# OpenHaldexC6-V1_1_2026-01-01.net
KiCad netlist of a schematic drawn in EasyEDA Pro
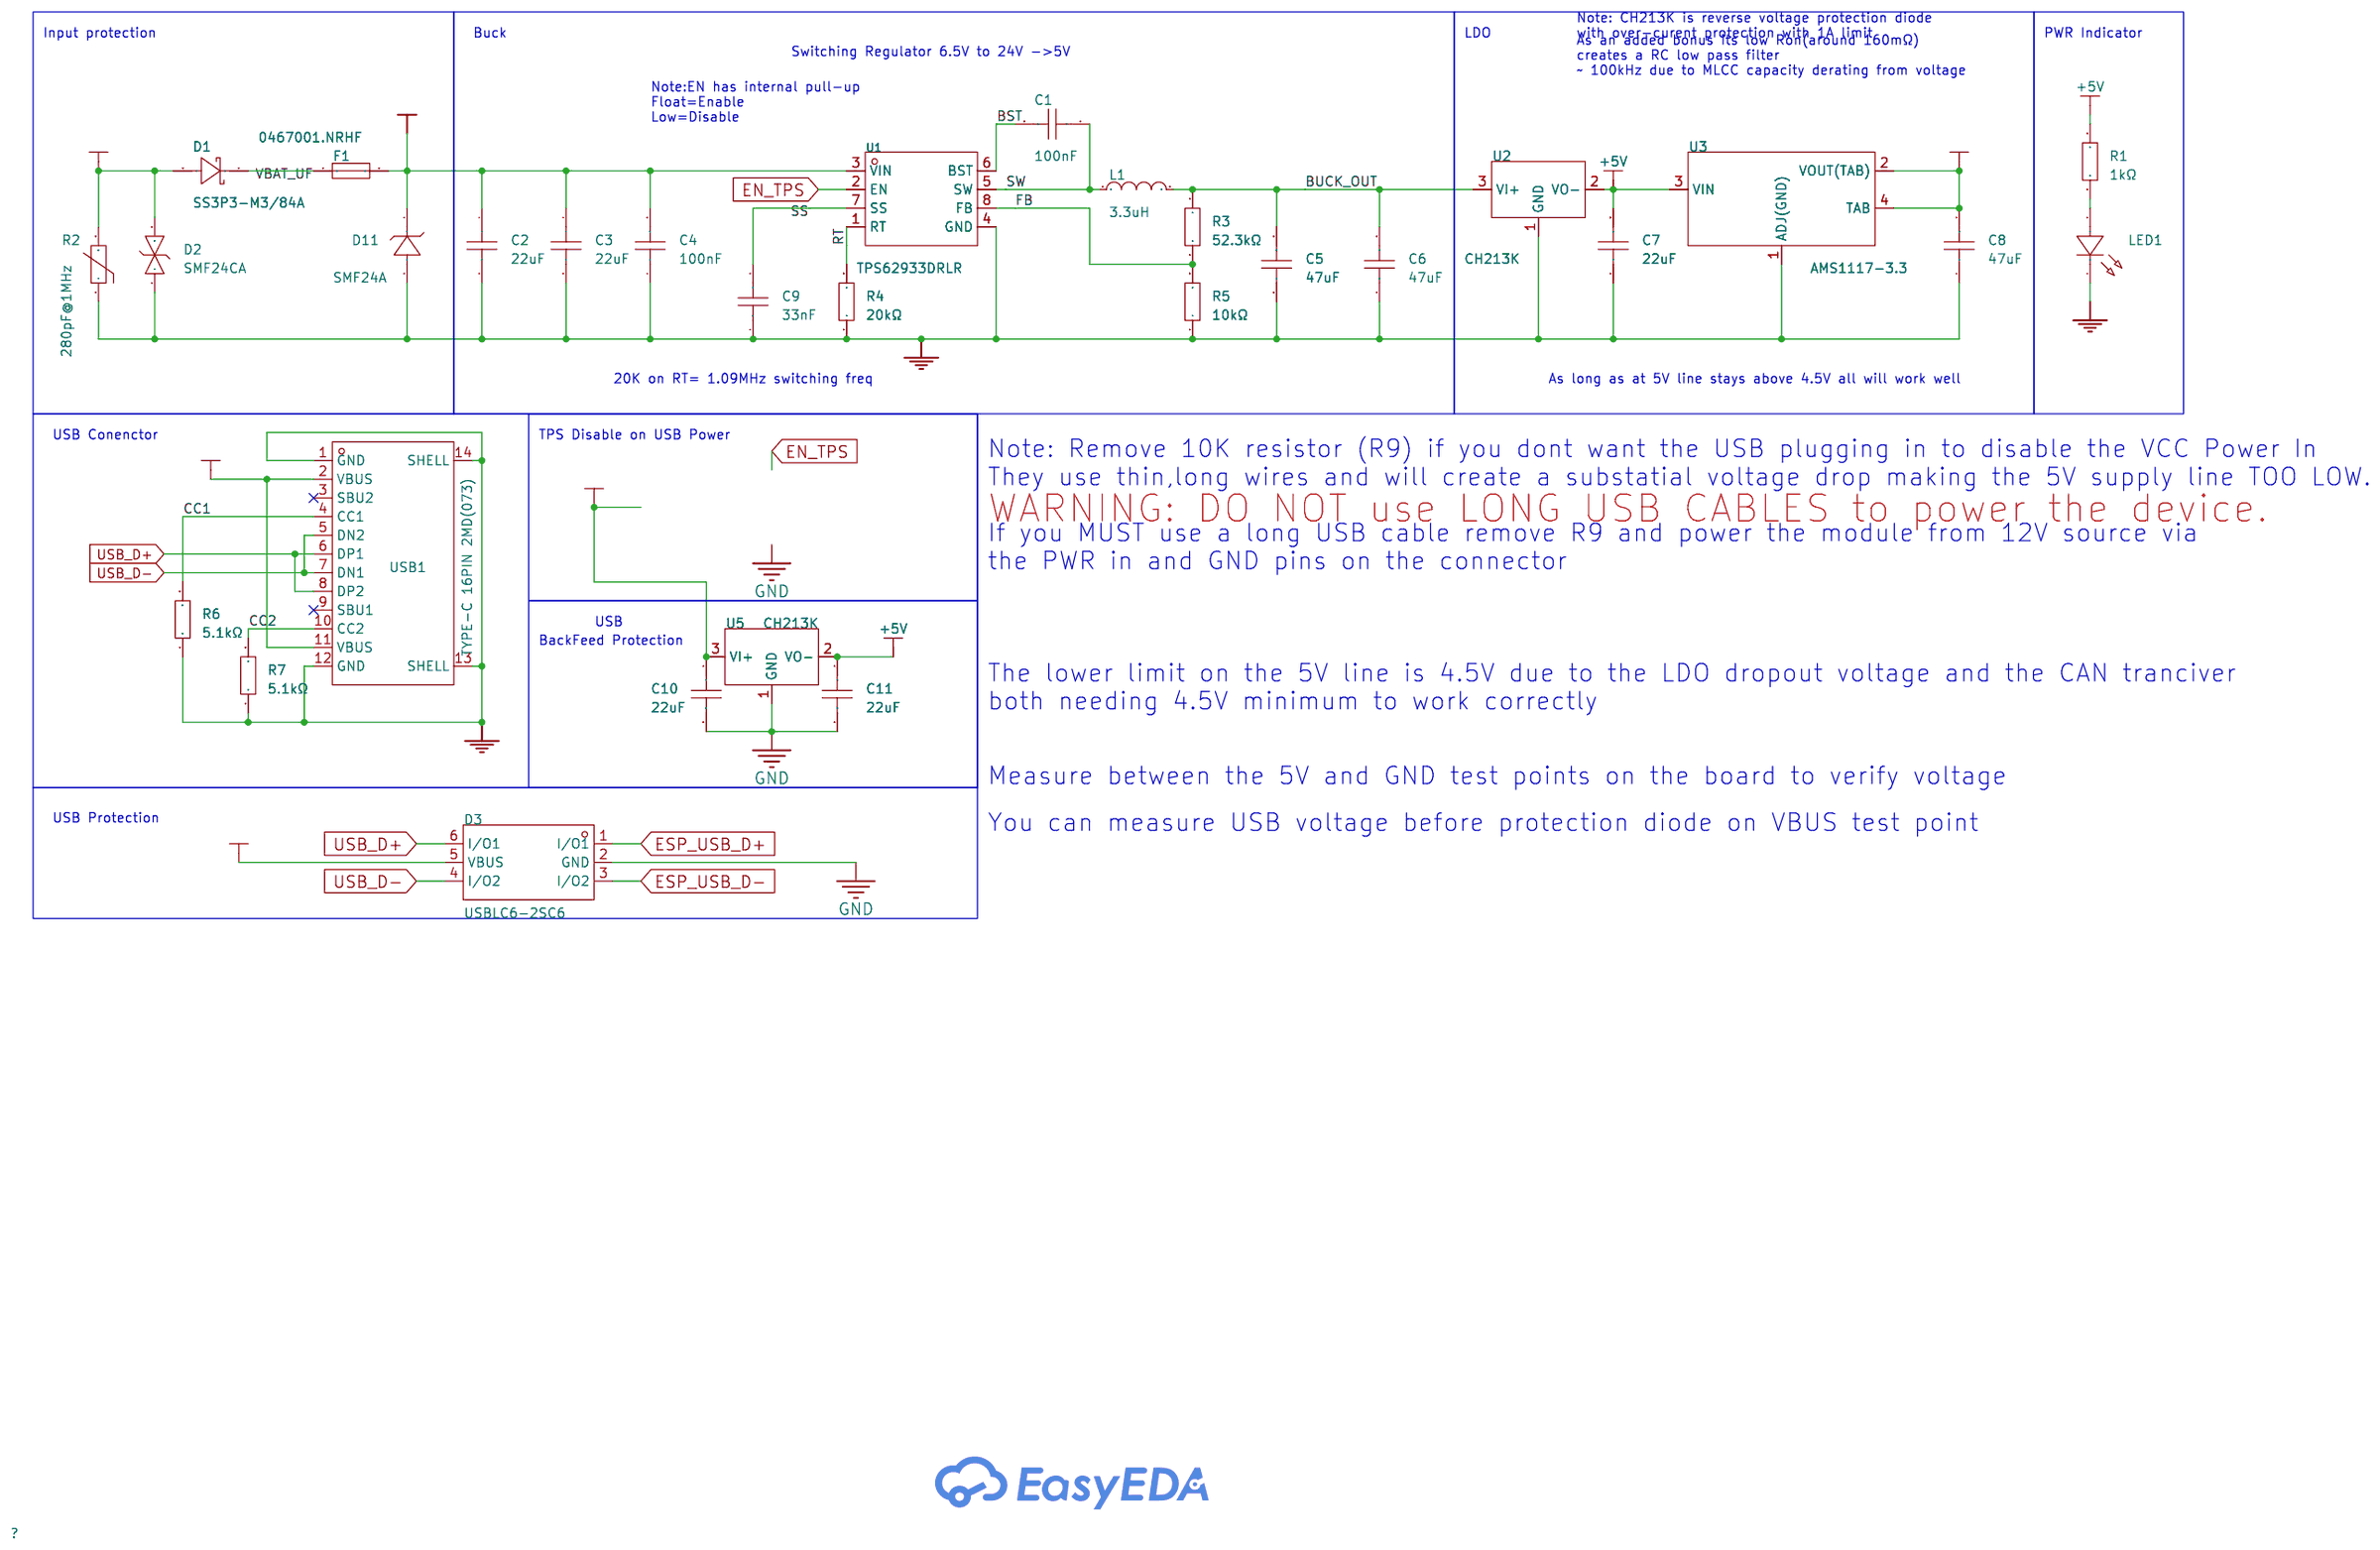
[diagram p0: Power +USB]
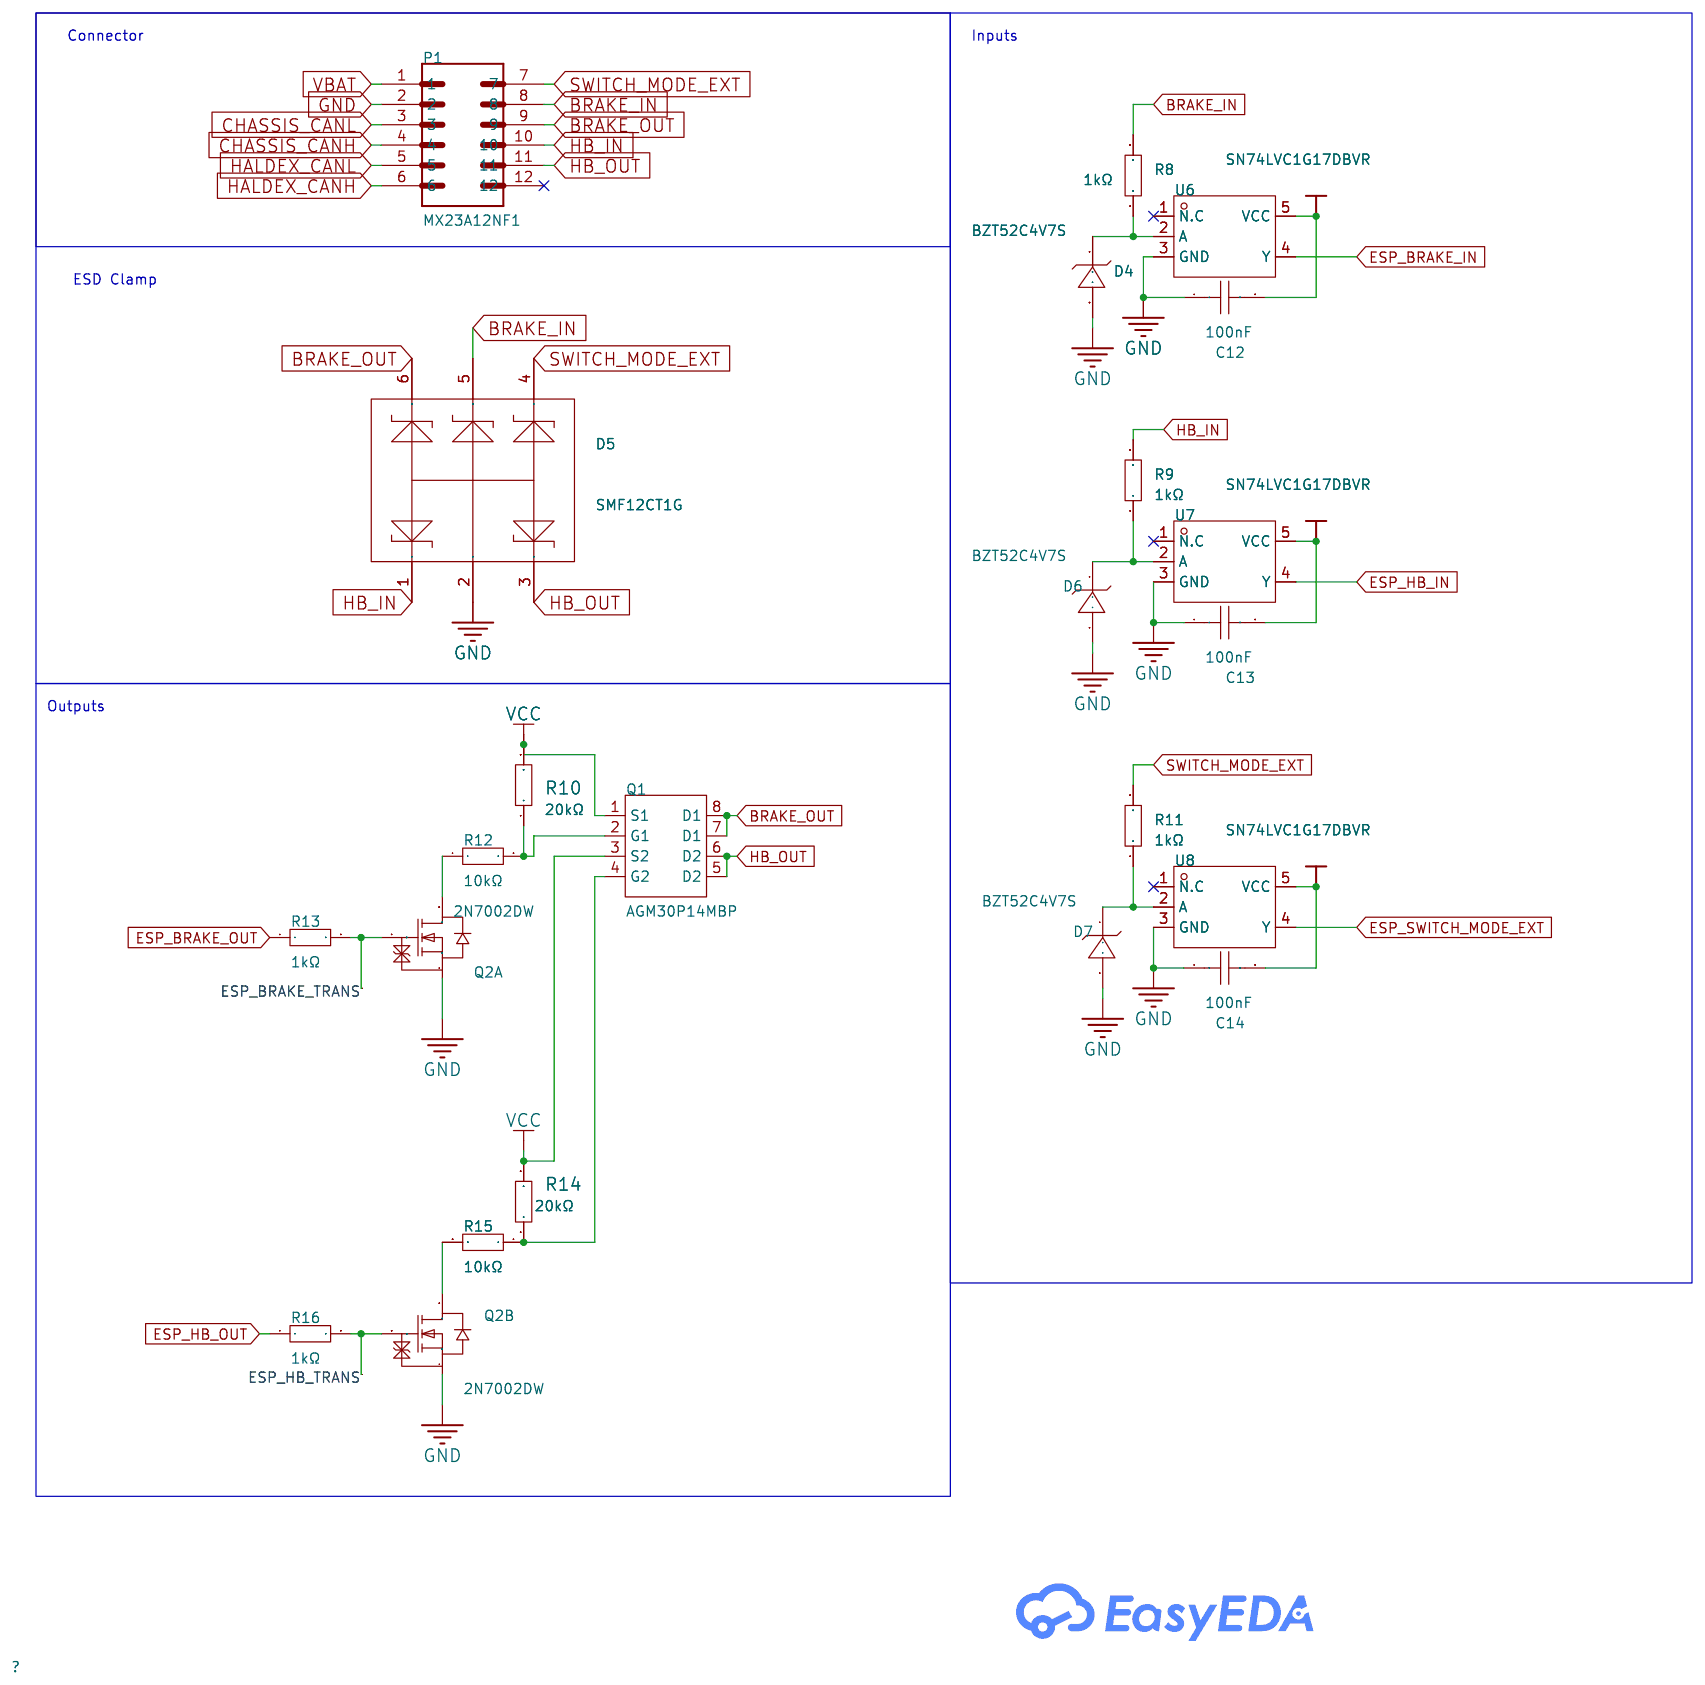
[diagram p1: Conn, Input + Output]
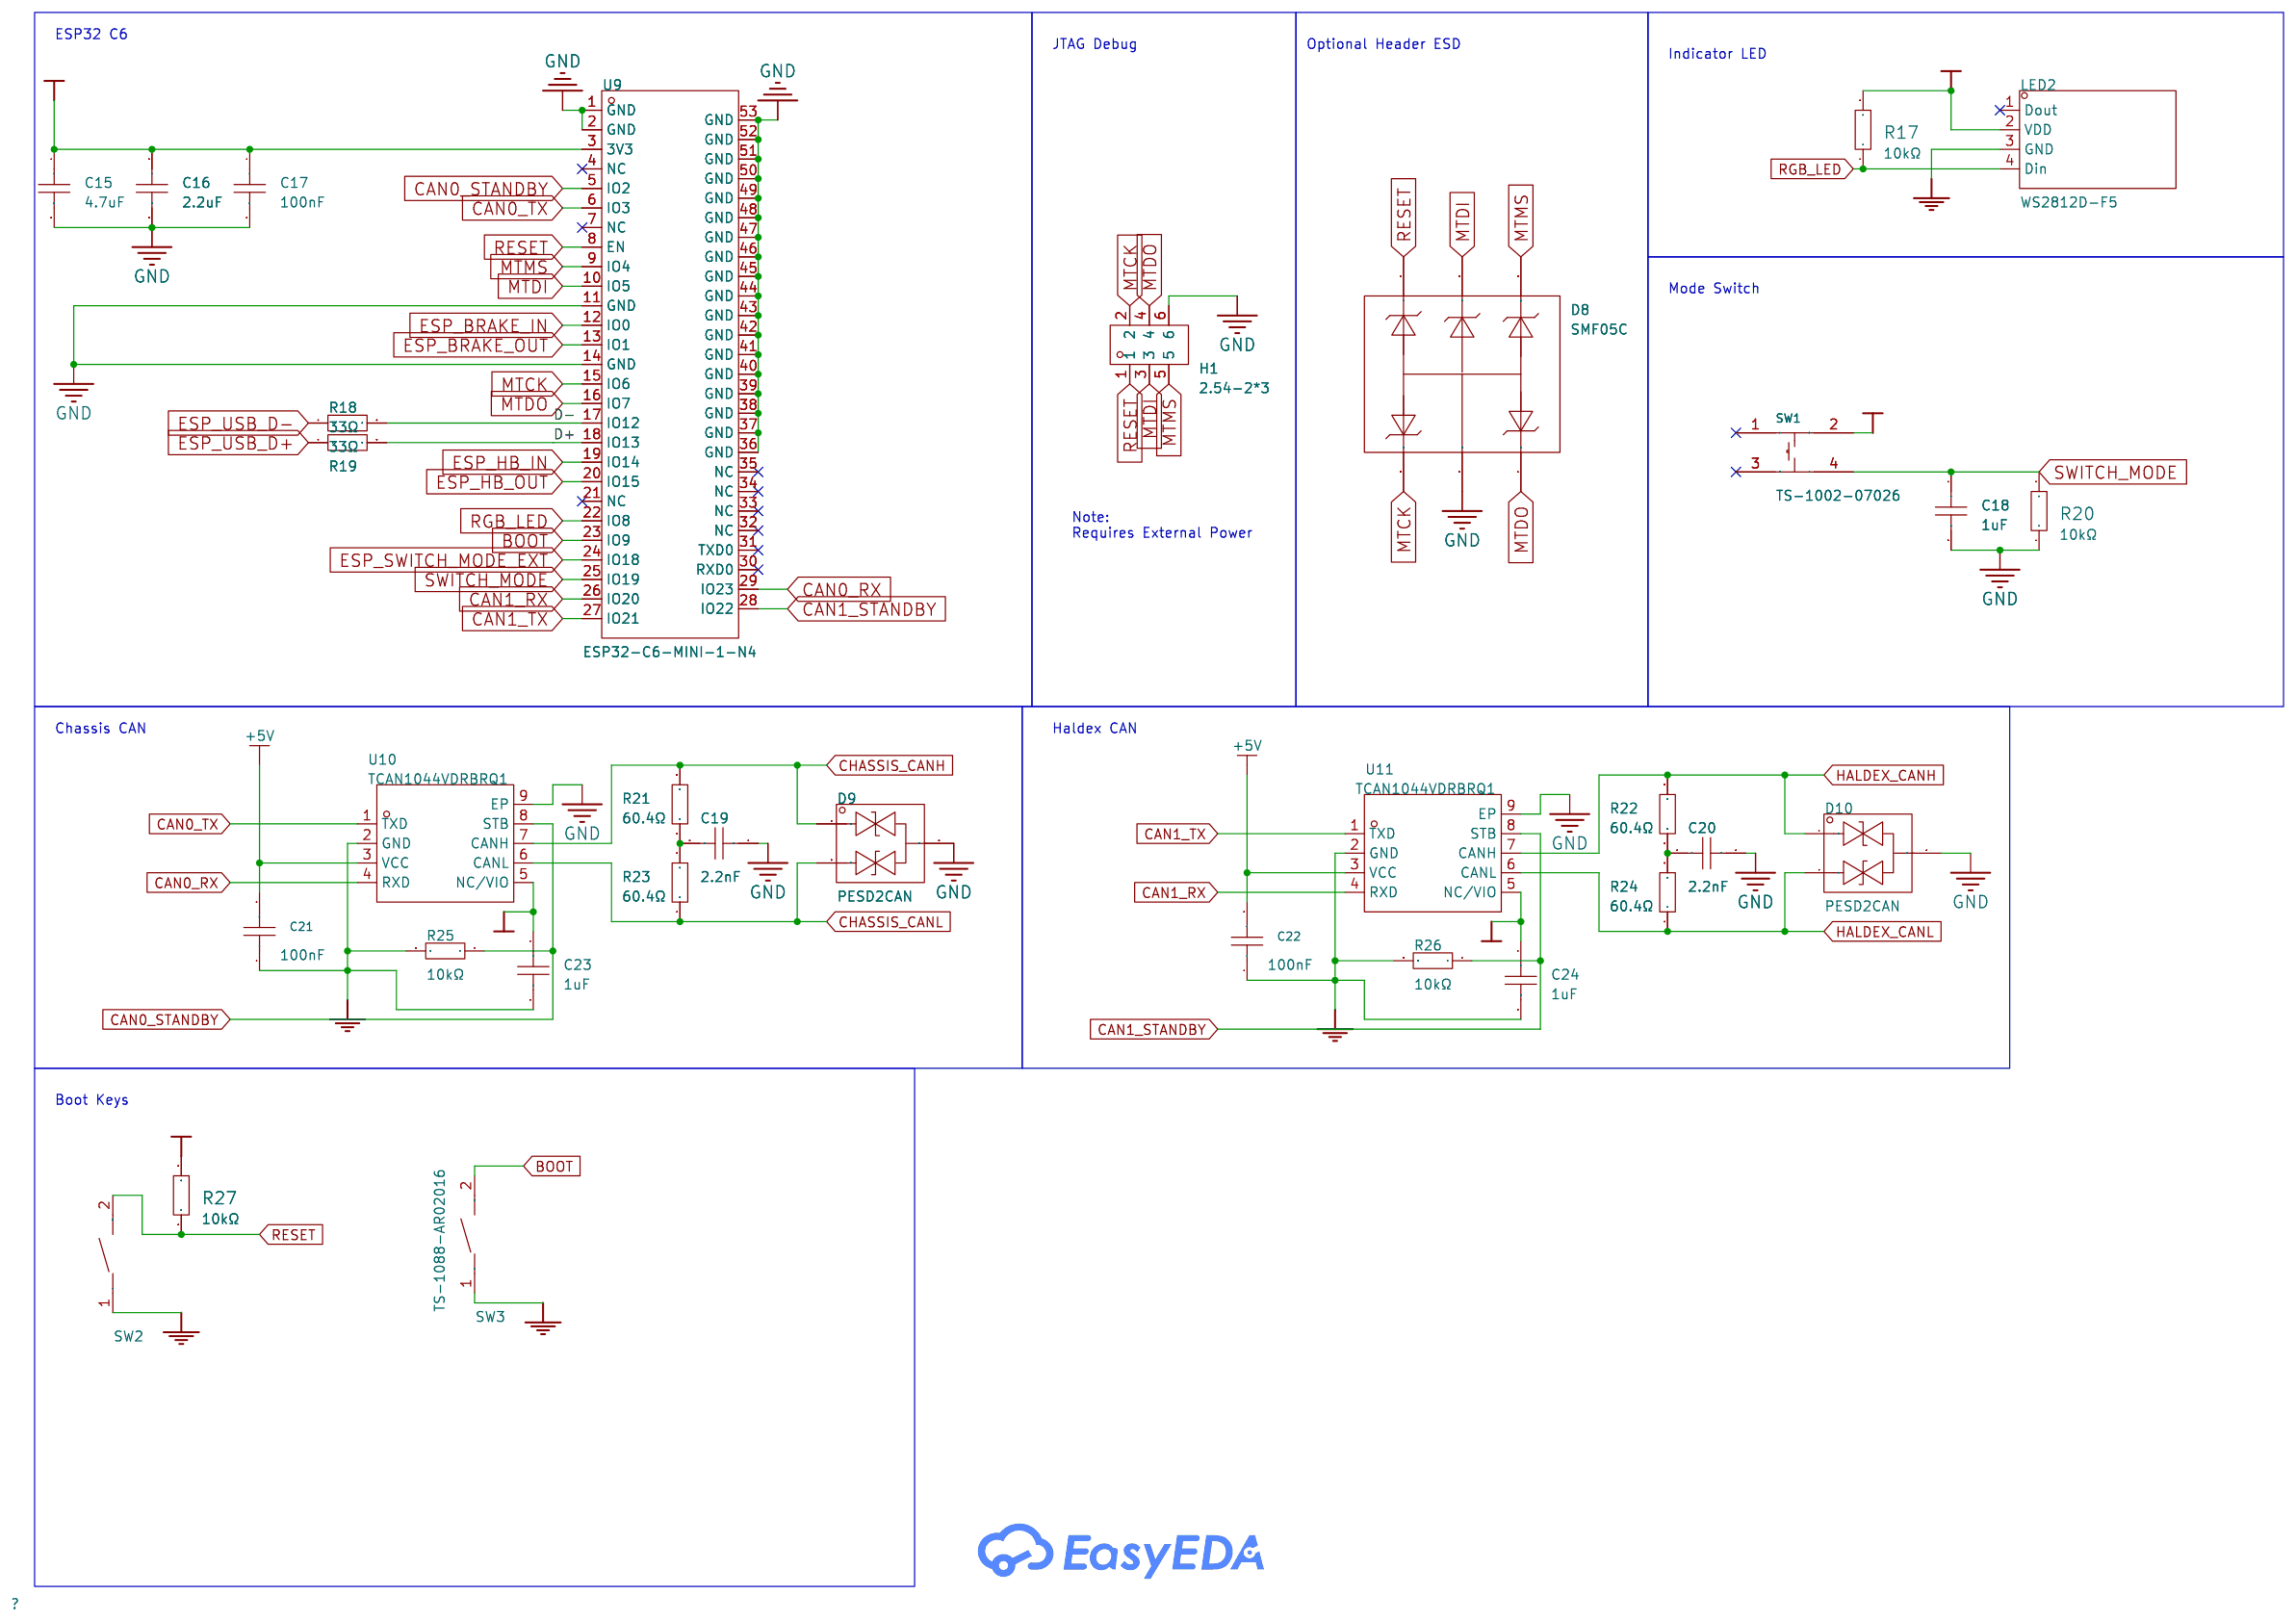
[diagram p2: MCU + CANBUS]

(export (version "E")
  (design (tool "Eeschema 10.0.6"))
  (components
    (comp (ref "C1")
      (value "100nF")
      (footprint "easyedapro:C0603")
      (description "Capacitance:100nF Tolerance:±10% Tolerance:±10% Voltage Rating:50V Temperature Coefficient:X7R")
      (fields
        (field (name "Manufacturer Part") "CL10B104KB8NNNC")
        (field (name "Manufacturer") "SAMSUNG(三星)")
      )
      (libsource (lib "easyedapro") (part "CC0603KRX7R9BB104"))
    )
    (comp (ref "C2")
      (value "22uF")
      (footprint "easyedapro:C0805")
      (fields
        (field (name "Manufacturer Part") "HGC0805R5226M350NSLJ")
        (field (name "Manufacturer") "Chinocera(华瓷)")
      )
      (libsource (lib "easyedapro") (part "HGC0805R5226M350NSLJ"))
    )
    (comp (ref "C3")
      (value "22uF")
      (footprint "easyedapro:C0805")
      (fields
        (field (name "Manufacturer Part") "HGC0805R5226M350NSLJ")
        (field (name "Manufacturer") "Chinocera(华瓷)")
      )
      (libsource (lib "easyedapro") (part "HGC0805R5226M350NSLJ"))
    )
    (comp (ref "C4")
      (value "100nF")
      (description "Capacitance:100nF Tolerance:±10% Tolerance:±10% Voltage Rating:50V Temperature Coefficient:X7R")
      (fields
        (field (name "Manufacturer Part") "CL10B104KB8NNNC")
        (field (name "Manufacturer") "SAMSUNG(三星)")
      )
      (libsource (lib "easyedapro") (part "CSA0603X7R104K500JT"))
    )
    (comp (ref "C5")
      (value "47uF")
      (footprint "easyedapro:C0805")
      (description "Capacitance:47uF Tolerance:±20% Tolerance:±20% Voltage Rating:10V Temperature Coefficient:X5R")
      (fields
        (field (name "Manufacturer Part") "CL21A476MPYNNWE")
        (field (name "Manufacturer") "SAMSUNG(三星)")
      )
      (libsource (lib "easyedapro") (part "CL21A476MPYNNWE"))
    )
    (comp (ref "C6")
      (value "47uF")
      (footprint "easyedapro:C0805")
      (description "Capacitance:47uF Tolerance:±20% Tolerance:±20% Voltage Rating:10V Temperature Coefficient:X5R")
      (fields
        (field (name "Manufacturer Part") "CL21A476MPYNNWE")
        (field (name "Manufacturer") "SAMSUNG(三星)")
      )
      (libsource (lib "easyedapro") (part "CL21A476MPYNNWE"))
    )
    (comp (ref "C7")
      (value "22uF")
      (footprint "easyedapro:C0805")
      (fields
        (field (name "Manufacturer Part") "HGC0805R5226M350NSLJ")
        (field (name "Manufacturer") "Chinocera(华瓷)")
      )
      (libsource (lib "easyedapro") (part "HGC0805R5226M350NSLJ"))
    )
    (comp (ref "C8")
      (value "47uF")
      (footprint "easyedapro:C0805")
      (description "Capacitance:47uF Tolerance:±20% Tolerance:±20% Voltage Rating:10V Temperature Coefficient:X5R")
      (fields
        (field (name "Manufacturer Part") "CL21A476MPYNNWE")
        (field (name "Manufacturer") "SAMSUNG(三星)")
      )
      (libsource (lib "easyedapro") (part "CL21A476MPYNNWE"))
    )
    (comp (ref "C9")
      (value "33nF")
      (description "Capacitance:33nF Tolerance:±10% Tolerance:±10% Voltage Rating:50V Temperature Coefficient:X7R")
      (fields
        (field (name "Manufacturer Part") "CL10B333KB8NNNC")
        (field (name "Manufacturer") "SAMSUNG(三星)")
      )
      (libsource (lib "easyedapro") (part "CSA0603X7R104K500JT"))
    )
    (comp (ref "C10")
      (value "22uF")
      (footprint "easyedapro:C0805")
      (fields
        (field (name "Manufacturer Part") "HGC0805R5226M350NSLJ")
        (field (name "Manufacturer") "Chinocera(华瓷)")
      )
      (libsource (lib "easyedapro") (part "HGC0805R5226M350NSLJ"))
    )
    (comp (ref "C11")
      (value "22uF")
      (footprint "easyedapro:C0805")
      (fields
        (field (name "Manufacturer Part") "HGC0805R5226M350NSLJ")
        (field (name "Manufacturer") "Chinocera(华瓷)")
      )
      (libsource (lib "easyedapro") (part "HGC0805R5226M350NSLJ"))
    )
    (comp (ref "D1")
      (value "SS3P3-M3/84A")
      (footprint "easyedapro:DO-220AA_L3.4-W2.0-LS3.9-RD")
      (fields (field (name "Manufacturer") "VISHAY(威世)"))
      (libsource (lib "easyedapro") (part "SS3P3-M3/84A"))
    )
    (comp (ref "D2")
      (value "SMF24CA")
      (footprint "easyedapro:SOD-123FL_L2.8-W1.8-LS3.7-BI")
      (fields (field (name "Manufacturer") "晶导微电子"))
      (libsource (lib "easyedapro") (part "SMF24CA_C353294"))
    )
    (comp (ref "D3")
      (value "USBLC6-2SC6")
      (footprint "easyedapro:SOT-23-6_L2.9-W1.6-P0.95-LS2.8-BL")
      (description "Maximum Clamping Voltage:15V Breakdown Voltage:6V Number of Lines:双路 Type:ESD")
      (fields (field (name "Manufacturer") "UMW(友台半导体)"))
      (libsource (lib "easyedapro") (part "USBLC6-2SC6_C2687116"))
    )
    (comp (ref "D11")
      (value "SMF24A")
      (footprint "easyedapro:SOD-123FL_L2.7-W1.8-LS3.8-RD")
      (fields (field (name "Manufacturer") "R+O(宏嘉诚)"))
      (libsource (lib "easyedapro") (part "SMF24A_C19077514"))
    )
    (comp (ref "F1")
      (value "0467001.NRHF")
      (footprint "easyedapro:F0603")
      (fields (field (name "Manufacturer") "Littelfuse(美国力特)"))
      (libsource (lib "easyedapro") (part "0467001.NRHF"))
    )
    (comp (ref "L1")
      (value "3.3uH")
      (footprint "easyedapro:IND-SMD_L5.4-W5.2_RS0530")
      (fields (field (name "Manufacturer Part") "RS0530-3R3MS") (field (name "Manufacturer") "Ruishen(瑞申电子)"))
      (libsource (lib "easyedapro") (part "RS0530-3R3MS"))
    )
    (comp (ref "LED1")
      (value "XL-1608UGC-04")
      (footprint "easyedapro:LED0603-RD_GREEN")
      (fields (field (name "Manufacturer") "XINGLIGHT(成兴光)"))
      (libsource (lib "easyedapro") (part "XL-1608UGC-04"))
    )
    (comp (ref "R1")
      (value "1kΩ")
      (footprint "easyedapro:R0603")
      (fields
        (field (name "Manufacturer Part") "0603WAF1001T5E")
        (field (name "Manufacturer") "UNI-ROYAL(厚声)")
      )
      (libsource (lib "easyedapro") (part "0603WAF2201T5E"))
    )
    (comp (ref "R2")
      (value "280pF@1MHz")
      (footprint "easyedapro:R0805")
      (fields (field (name "Manufacturer Part") "FPV201209E260PKT") (field (name "Manufacturer") "FH(风华)"))
      (libsource (lib "easyedapro") (part "FPV201209E260PKT"))
    )
    (comp (ref "R3")
      (value "52.3kΩ")
      (footprint "easyedapro:R0603")
      (fields
        (field (name "Manufacturer Part") "0603WAF5232T5E")
        (field (name "Manufacturer") "UNI-ROYAL(厚声)")
      )
      (libsource (lib "easyedapro") (part "Res"))
    )
    (comp (ref "R4")
      (value "20kΩ")
      (footprint "easyedapro:R0603")
      (fields
        (field (name "Manufacturer Part") "0603WAF2002T5E")
        (field (name "Manufacturer") "UNI-ROYAL(厚声)")
      )
      (libsource (lib "easyedapro") (part "Res"))
    )
    (comp (ref "R5")
      (value "10kΩ")
      (footprint "easyedapro:R0603")
      (fields
        (field (name "Manufacturer Part") "0603WAF1002T5E")
        (field (name "Manufacturer") "UNI-ROYAL(厚声)")
      )
      (libsource (lib "easyedapro") (part "Res"))
    )
    (comp (ref "R6")
      (value "5.1kΩ")
      (footprint "easyedapro:R0603")
      (fields
        (field (name "Manufacturer Part") "0603WAF5101T5E")
        (field (name "Manufacturer") "UNI-ROYAL(厚声)")
      )
      (libsource (lib "easyedapro") (part "Res"))
    )
    (comp (ref "R7")
      (value "5.1kΩ")
      (footprint "easyedapro:R0603")
      (fields
        (field (name "Manufacturer Part") "0603WAF5101T5E")
        (field (name "Manufacturer") "UNI-ROYAL(厚声)")
      )
      (libsource (lib "easyedapro") (part "Res"))
    )
    (comp (ref "U1")
      (value "TPS62933DRLR")
      (footprint "easyedapro:SOT-583-8_L2.1-W1.2-P0.50-LS1.6-BR")
      (fields (field (name "Manufacturer") "TI(德州仪器)"))
      (libsource (lib "easyedapro") (part "TPS62933DRLR"))
    )
    (comp (ref "U2")
      (value "CH213K")
      (footprint "easyedapro:SOT-23-3_L2.9-W1.6-P1.90-LS2.8-BR")
      (fields (field (name "Manufacturer") "WCH(南京沁恒)"))
      (libsource (lib "easyedapro") (part "CH213K"))
    )
    (comp (ref "U3")
      (value "AMS1117-3.3")
      (footprint "easyedapro:SOT-223-4_L6.5-W3.5-P2.30-LS7.0-BR")
      (fields (field (name "Manufacturer") "UMW(友台半导体)"))
      (libsource (lib "easyedapro") (part "AMS1117-3.3_C347222"))
    )
    (comp (ref "U5")
      (value "CH213K")
      (footprint "easyedapro:SOT-23-3_L2.9-W1.6-P1.90-LS2.8-BR")
      (fields (field (name "Manufacturer") "WCH(南京沁恒)"))
      (libsource (lib "easyedapro") (part "CH213K"))
    )
    (comp (ref "USB1")
      (value "TYPE-C 16PIN 2MD(073)")
      (footprint "easyedapro:USB-C-SMD_TYPE-C-6PIN-2MD-073")
      (fields (field (name "Manufacturer") "SHOU HAN(首韩)"))
      (libsource (lib "easyedapro") (part "TYPE-C 16PIN 2MD(073)"))
    )
    (comp (ref "C12")
      (value "100nF")
      (footprint "easyedapro:C0603")
      (description "Capacitance:100nF Tolerance:±10% Tolerance:±10% Voltage Rating:50V Temperature Coefficient:X7R")
      (fields
        (field (name "Manufacturer Part") "CL10B104KB8NNNC")
        (field (name "Manufacturer") "SAMSUNG(三星)")
      )
      (libsource (lib "easyedapro") (part "CC0603KRX7R9BB104"))
    )
    (comp (ref "C13")
      (value "100nF")
      (footprint "easyedapro:C0603")
      (description "Capacitance:100nF Tolerance:±10% Tolerance:±10% Voltage Rating:50V Temperature Coefficient:X7R")
      (fields
        (field (name "Manufacturer Part") "CL10B104KB8NNNC")
        (field (name "Manufacturer") "SAMSUNG(三星)")
      )
      (libsource (lib "easyedapro") (part "CC0603KRX7R9BB104"))
    )
    (comp (ref "C14")
      (value "100nF")
      (footprint "easyedapro:C0603")
      (description "Capacitance:100nF Tolerance:±10% Tolerance:±10% Voltage Rating:50V Temperature Coefficient:X7R")
      (fields
        (field (name "Manufacturer Part") "CL10B104KB8NNNC")
        (field (name "Manufacturer") "SAMSUNG(三星)")
      )
      (libsource (lib "easyedapro") (part "CC0603KRX7R9BB104"))
    )
    (comp (ref "D4")
      (value "BZT52C4V7S")
      (footprint "easyedapro:SOD-323_L1.8-W1.3-LS2.5-RD")
      (fields (field (name "Manufacturer") "晶导微电子"))
      (libsource (lib "easyedapro") (part "BZT52C4V7S_C353517"))
    )
    (comp (ref "D5")
      (value "SMF12CT1G")
      (footprint "easyedapro:SOT-363_L2.0-W1.3-P0.65-LS2.1-BR")
      (fields (field (name "Manufacturer") "TECH PUBLIC(台舟)"))
      (libsource (lib "easyedapro") (part "SMF12CT1G_C2999118"))
    )
    (comp (ref "D6")
      (value "BZT52C4V7S")
      (footprint "easyedapro:SOD-323_L1.8-W1.3-LS2.5-RD")
      (fields (field (name "Manufacturer") "晶导微电子"))
      (libsource (lib "easyedapro") (part "BZT52C4V7S_C353517"))
    )
    (comp (ref "D7")
      (value "BZT52C4V7S")
      (footprint "easyedapro:SOD-323_L1.8-W1.3-LS2.5-RD")
      (fields (field (name "Manufacturer") "晶导微电子"))
      (libsource (lib "easyedapro") (part "BZT52C4V7S_C353517"))
    )
    (comp (ref "P1")
      (value "MX23A12NF1")
      (fields (field (name "Manufacturer") "JAE(日本航空电子)"))
      (libsource (lib "easyedapro") (part "MX23A12NF1_MX23A12NF1_"))
    )
    (comp (ref "Q1")
      (value "AGM30P14MBP")
      (footprint "easyedapro:DFN-8_L3.2-W3.1-P0.65-LS3.4-BL-1")
      (fields (field (name "Manufacturer") "AGMSEMI(芯控源)"))
      (libsource (lib "easyedapro") (part "AGM30P14MBP"))
    )
    (comp (ref "Q2")
      (value "2N7002DW")
      (footprint "easyedapro:SOT-363-6_L2.0-W1.3-P0.65-LS2.1-BL")
      (fields (field (name "Manufacturer") "Hottech(合科泰)"))
      (libsource (lib "easyedapro") (part "2N7002DW_C5190214"))
    )
    (comp (ref "R8")
      (value "1kΩ")
      (footprint "easyedapro:R0603")
      (fields
        (field (name "Manufacturer Part") "0603WAF1001T5E")
        (field (name "Manufacturer") "UNI-ROYAL(厚声)")
      )
      (libsource (lib "easyedapro") (part "0603WAF1001T5E"))
    )
    (comp (ref "R9")
      (value "1kΩ")
      (footprint "easyedapro:R0603")
      (fields
        (field (name "Manufacturer Part") "0603WAF1001T5E")
        (field (name "Manufacturer") "UNI-ROYAL(厚声)")
      )
      (libsource (lib "easyedapro") (part "0603WAF1001T5E"))
    )
    (comp (ref "R10")
      (value "20kΩ")
      (footprint "easyedapro:R0603")
      (fields
        (field (name "Manufacturer Part") "0603WAF2002T5E")
        (field (name "Manufacturer") "UNI-ROYAL(厚声)")
      )
      (libsource (lib "easyedapro") (part "0603WAF1002T5E"))
    )
    (comp (ref "R11")
      (value "1kΩ")
      (footprint "easyedapro:R0603")
      (fields
        (field (name "Manufacturer Part") "0603WAF1001T5E")
        (field (name "Manufacturer") "UNI-ROYAL(厚声)")
      )
      (libsource (lib "easyedapro") (part "0603WAF1001T5E"))
    )
    (comp (ref "R12")
      (value "10kΩ")
      (footprint "easyedapro:R0603")
      (fields
        (field (name "Manufacturer Part") "0603WAF1002T5E")
        (field (name "Manufacturer") "UNI-ROYAL(厚声)")
      )
      (libsource (lib "easyedapro") (part "Res"))
    )
    (comp (ref "R13")
      (value "1kΩ")
      (footprint "easyedapro:R0603")
      (fields
        (field (name "Manufacturer Part") "0603WAF1001T5E")
        (field (name "Manufacturer") "UNI-ROYAL(厚声)")
      )
      (libsource (lib "easyedapro") (part "0603WAF3300T5E"))
    )
    (comp (ref "R14")
      (value "20kΩ")
      (footprint "easyedapro:R0603")
      (fields
        (field (name "Manufacturer Part") "0603WAF2002T5E")
        (field (name "Manufacturer") "UNI-ROYAL(厚声)")
      )
      (libsource (lib "easyedapro") (part "0603WAF1002T5E"))
    )
    (comp (ref "R15")
      (value "10kΩ")
      (footprint "easyedapro:R0603")
      (fields
        (field (name "Manufacturer Part") "0603WAF1002T5E")
        (field (name "Manufacturer") "UNI-ROYAL(厚声)")
      )
      (libsource (lib "easyedapro") (part "Res"))
    )
    (comp (ref "R16")
      (value "1kΩ")
      (footprint "easyedapro:R0603")
      (fields
        (field (name "Manufacturer Part") "0603WAF1001T5E")
        (field (name "Manufacturer") "UNI-ROYAL(厚声)")
      )
      (libsource (lib "easyedapro") (part "0603WAF3300T5E"))
    )
    (comp (ref "U6")
      (value "SN74LVC1G17DBVR")
      (footprint "easyedapro:SOT-23-5_L3.0-W1.5-P0.95-LS2.8-BL")
      (fields (field (name "Manufacturer") "TECH PUBLIC(台舟)"))
      (libsource (lib "easyedapro") (part "SN74LVC1G17DBVR_C19829662"))
    )
    (comp (ref "U7")
      (value "SN74LVC1G17DBVR")
      (footprint "easyedapro:SOT-23-5_L3.0-W1.5-P0.95-LS2.8-BL")
      (fields (field (name "Manufacturer") "TECH PUBLIC(台舟)"))
      (libsource (lib "easyedapro") (part "SN74LVC1G17DBVR_C19829662"))
    )
    (comp (ref "U8")
      (value "SN74LVC1G17DBVR")
      (footprint "easyedapro:SOT-23-5_L3.0-W1.5-P0.95-LS2.8-BL")
      (fields (field (name "Manufacturer") "TECH PUBLIC(台舟)"))
      (libsource (lib "easyedapro") (part "SN74LVC1G17DBVR_C19829662"))
    )
    (comp (ref "C15")
      (value "4.7uF")
      (footprint "easyedapro:C0603")
      (description "Capacitance:4.7uF Tolerance:±10% Tolerance:±10% Voltage Rating:10V Temperature Coefficient:X5R")
      (fields
        (field (name "Manufacturer Part") "CL10A475KP8NNNC")
        (field (name "Manufacturer") "SAMSUNG(三星)")
      )
      (libsource (lib "easyedapro") (part "CAP"))
    )
    (comp (ref "C16")
      (value "2.2uF")
      (footprint "easyedapro:C0603")
      (description "Capacitance:2.2uF Tolerance:±10% Tolerance:±10% Voltage Rating:16V Temperature Coefficient:X5R")
      (fields
        (field (name "Manufacturer Part") "CL10A225KO8NNNC")
        (field (name "Manufacturer") "SAMSUNG(三星)")
      )
      (libsource (lib "easyedapro") (part "CAP"))
    )
    (comp (ref "C17")
      (value "100nF")
      (footprint "easyedapro:C0603")
      (description "Capacitance:100nF Tolerance:±10% Tolerance:±10% Voltage Rating:50V Temperature Coefficient:X7R")
      (fields
        (field (name "Manufacturer Part") "CL10B104KB8NNNC")
        (field (name "Manufacturer") "SAMSUNG(三星)")
      )
      (libsource (lib "easyedapro") (part "CAP"))
    )
    (comp (ref "C18")
      (value "1uF")
      (footprint "easyedapro:C0603")
      (description "Capacitance:1uF Tolerance:±10% Tolerance:±10% Voltage Rating:50V Temperature Coefficient:X7R")
      (fields
        (field (name "Manufacturer Part") "CL10B105KB8NQNC")
        (field (name "Manufacturer") "SAMSUNG(三星)")
      )
      (libsource (lib "easyedapro") (part "CL10B105KB8NQNC"))
    )
    (comp (ref "C19")
      (value "2.2nF")
      (footprint "easyedapro:C0603")
      (description "Capacitance:2.2nF Tolerance:±5% Tolerance:±5% Voltage Rating:50V Temperature Coefficient:C0G")
      (fields
        (field (name "Manufacturer Part") "CL10C222JB8NNNC")
        (field (name "Manufacturer") "SAMSUNG(三星)")
      )
      (libsource (lib "easyedapro") (part "CAP"))
    )
    (comp (ref "C20")
      (value "2.2nF")
      (footprint "easyedapro:C0603")
      (description "Capacitance:2.2nF Tolerance:±5% Tolerance:±5% Voltage Rating:50V Temperature Coefficient:C0G")
      (fields
        (field (name "Manufacturer Part") "CL10C222JB8NNNC")
        (field (name "Manufacturer") "SAMSUNG(三星)")
      )
      (libsource (lib "easyedapro") (part "CAP"))
    )
    (comp (ref "C21")
      (value "100nF")
      (footprint "easyedapro:C0603")
      (description "Capacitance:100nF Tolerance:±10% Tolerance:±10% Voltage Rating:50V Temperature Coefficient:X7R")
      (fields
        (field (name "Manufacturer Part") "CL10B104KB8NNNC")
        (field (name "Manufacturer") "SAMSUNG(三星)")
      )
      (libsource (lib "easyedapro") (part "CL10B104KB8NNNC"))
    )
    (comp (ref "C22")
      (value "100nF")
      (footprint "easyedapro:C0603")
      (description "Capacitance:100nF Tolerance:±10% Tolerance:±10% Voltage Rating:50V Temperature Coefficient:X7R")
      (fields
        (field (name "Manufacturer Part") "CL10B104KB8NNNC")
        (field (name "Manufacturer") "SAMSUNG(三星)")
      )
      (libsource (lib "easyedapro") (part "CL10B104KB8NNNC"))
    )
    (comp (ref "C23")
      (value "1uF")
      (footprint "easyedapro:C0603")
      (description "Capacitance:1uF Tolerance:±10% Tolerance:±10% Voltage Rating:50V Temperature Coefficient:X7R")
      (fields
        (field (name "Manufacturer Part") "CL10B105KB8NQNC")
        (field (name "Manufacturer") "SAMSUNG(三星)")
      )
      (libsource (lib "easyedapro") (part "CAP"))
    )
    (comp (ref "C24")
      (value "1uF")
      (footprint "easyedapro:C0603")
      (description "Capacitance:1uF Tolerance:±10% Tolerance:±10% Voltage Rating:50V Temperature Coefficient:X7R")
      (fields
        (field (name "Manufacturer Part") "CL10B105KB8NQNC")
        (field (name "Manufacturer") "SAMSUNG(三星)")
      )
      (libsource (lib "easyedapro") (part "CAP"))
    )
    (comp (ref "D8")
      (value "SMF05C")
      (footprint "easyedapro:SC-70-6_L2.0-W1.3-P0.65-LS2.1-BR")
      (fields (field (name "Manufacturer") "TECH PUBLIC(台舟)"))
      (libsource (lib "easyedapro") (part "SMF05C_C558425"))
    )
    (comp (ref "D9")
      (value "PESD2CAN")
      (footprint "easyedapro:SOT-23-3_L2.9-W1.3-P1.90-LS2.4-BR")
      (fields (field (name "Manufacturer") "DOWO(东沃)"))
      (libsource (lib "easyedapro") (part "PESD2CAN"))
    )
    (comp (ref "D10")
      (value "PESD2CAN")
      (footprint "easyedapro:SOT-23-3_L2.9-W1.3-P1.90-LS2.4-BR")
      (fields (field (name "Manufacturer") "DOWO(东沃)"))
      (libsource (lib "easyedapro") (part "PESD2CAN"))
    )
    (comp (ref "H1")
      (value "2.54-2*3")
      (footprint "easyedapro:HDR-TH_6P-P2.54-V-R2-C3-S2.54_A2541WV-2X3P")
      (fields (field (name "Manufacturer") "ZHOURI(洲日)"))
      (libsource (lib "easyedapro") (part "2.54-2*3"))
    )
    (comp (ref "LED2")
      (value "WS2812D-F5")
      (footprint "easyedapro:LED-TH_4P-BD5.8-P1.30")
      (fields (field (name "Manufacturer") "worldsemi"))
      (libsource (lib "easyedapro") (part "WS2812D-F5"))
    )
    (comp (ref "R17")
      (value "10kΩ")
      (footprint "easyedapro:R0603")
      (fields
        (field (name "Manufacturer Part") "0603WAF1002T5E")
        (field (name "Manufacturer") "UNI-ROYAL(厚声)")
      )
      (libsource (lib "easyedapro") (part "0603WAF1002T5E"))
    )
    (comp (ref "R18")
      (value "33Ω")
      (footprint "easyedapro:R0603")
      (fields
        (field (name "Manufacturer Part") "0603WAF330JT5E")
        (field (name "Manufacturer") "UNI-ROYAL(厚声)")
      )
      (libsource (lib "easyedapro") (part "Res"))
    )
    (comp (ref "R19")
      (value "33Ω")
      (footprint "easyedapro:R0603")
      (fields
        (field (name "Manufacturer Part") "0603WAF330JT5E")
        (field (name "Manufacturer") "UNI-ROYAL(厚声)")
      )
      (libsource (lib "easyedapro") (part "Res"))
    )
    (comp (ref "R20")
      (value "10kΩ")
      (footprint "easyedapro:R0603")
      (fields
        (field (name "Manufacturer Part") "0603WAF1002T5E")
        (field (name "Manufacturer") "UNI-ROYAL(厚声)")
      )
      (libsource (lib "easyedapro") (part "0603WAF1002T5E"))
    )
    (comp (ref "R21")
      (value "60.4Ω")
      (footprint "easyedapro:R0603")
      (fields (field (name "Manufacturer Part") "RC0603FR-0760R4L") (field (name "Manufacturer") "YAGEO(国巨)"))
      (libsource (lib "easyedapro") (part "RC0603FR-0760R4L"))
    )
    (comp (ref "R22")
      (value "60.4Ω")
      (footprint "easyedapro:R0603")
      (fields (field (name "Manufacturer Part") "RC0603FR-0760R4L") (field (name "Manufacturer") "YAGEO(国巨)"))
      (libsource (lib "easyedapro") (part "RC0603FR-0760R4L"))
    )
    (comp (ref "R23")
      (value "60.4Ω")
      (footprint "easyedapro:R0603")
      (fields (field (name "Manufacturer Part") "RC0603FR-0760R4L") (field (name "Manufacturer") "YAGEO(国巨)"))
      (libsource (lib "easyedapro") (part "RC0603FR-0760R4L"))
    )
    (comp (ref "R24")
      (value "60.4Ω")
      (footprint "easyedapro:R0603")
      (fields (field (name "Manufacturer Part") "RC0603FR-0760R4L") (field (name "Manufacturer") "YAGEO(国巨)"))
      (libsource (lib "easyedapro") (part "RC0603FR-0760R4L"))
    )
    (comp (ref "R25")
      (value "10kΩ")
      (footprint "easyedapro:R0603")
      (fields
        (field (name "Manufacturer Part") "0603WAF1002T5E")
        (field (name "Manufacturer") "UNI-ROYAL(厚声)")
      )
      (libsource (lib "easyedapro") (part "0603WAF1002T5E"))
    )
    (comp (ref "R26")
      (value "10kΩ")
      (footprint "easyedapro:R0603")
      (fields
        (field (name "Manufacturer Part") "0603WAF1002T5E")
        (field (name "Manufacturer") "UNI-ROYAL(厚声)")
      )
      (libsource (lib "easyedapro") (part "0603WAF1002T5E"))
    )
    (comp (ref "R27")
      (value "10kΩ")
      (footprint "easyedapro:R0603")
      (fields
        (field (name "Manufacturer Part") "0603WAF1002T5E")
        (field (name "Manufacturer") "UNI-ROYAL(厚声)")
      )
      (libsource (lib "easyedapro") (part "0603WAF1002T5E"))
    )
    (comp (ref "SW1")
      (value "TS-1002-07026")
      (footprint "easyedapro:SW-TH_4P-L6.0-W6.0-P4.50-LS6.5")
      (fields (field (name "Manufacturer") "XUNPU(讯普)"))
      (libsource (lib "easyedapro") (part "TS-1002-07026"))
    )
    (comp (ref "SW2")
      (value "TS-1088-AR02016")
      (footprint "easyedapro:SW-SMD_L3.9-W3.0-P4.45")
      (fields (field (name "Manufacturer") "XUNPU(讯普)"))
      (libsource (lib "easyedapro") (part "TS-1088-AR02016"))
    )
    (comp (ref "SW3")
      (value "TS-1088-AR02016")
      (footprint "easyedapro:SW-SMD_L3.9-W3.0-P4.45")
      (fields (field (name "Manufacturer") "XUNPU(讯普)"))
      (libsource (lib "easyedapro") (part "TS-1088-AR02016"))
    )
    (comp (ref "U9")
      (value "ESP32-C6-MINI-1-N4")
      (footprint "easyedapro:WIFIM-SMD_61P-L16.6-W13.2-P0.80-ESP32-C6-MINI-1-N4")
      (fields (field (name "Manufacturer") "ESPRESSIF(乐鑫)"))
      (libsource (lib "easyedapro") (part "ESP32-C6-MINI-1-N4"))
    )
    (comp (ref "U10")
      (value "TCAN1044VDRBRQ1")
      (footprint "easyedapro:VSON-8_L3.0-W3.0-P0.65-BR-EP")
      (fields (field (name "Manufacturer") "TI(德州仪器)"))
      (libsource (lib "easyedapro") (part "TCAN1044VDRBRQ1"))
    )
    (comp (ref "U11")
      (value "TCAN1044VDRBRQ1")
      (footprint "easyedapro:VSON-8_L3.0-W3.0-P0.65-BR-EP")
      (fields (field (name "Manufacturer") "TI(德州仪器)"))
      (libsource (lib "easyedapro") (part "TCAN1044VDRBRQ1"))
    )
  )
  (nets
    (net (code "1") (name "+3.3V") (class "Default")
      (node (ref "C12") (pin "2") (pinfunction "2_2") (pintype "unspecified"))
      (node (ref "C13") (pin "2") (pinfunction "2_2") (pintype "unspecified"))
      (node (ref "C14") (pin "2") (pinfunction "2_2") (pintype "unspecified"))
      (node (ref "C15") (pin "1") (pinfunction "1_1") (pintype "input"))
      (node (ref "C16") (pin "1") (pinfunction "1_1") (pintype "input"))
      (node (ref "C17") (pin "1") (pinfunction "1_1") (pintype "input"))
      (node (ref "C23") (pin "1") (pinfunction "1_1") (pintype "input"))
      (node (ref "C24") (pin "1") (pinfunction "1_1") (pintype "input"))
      (node (ref "C8") (pin "2") (pinfunction "2_2") (pintype "unspecified"))
      (node (ref "LED2") (pin "2") (pinfunction "VDD_2") (pintype "unspecified"))
      (node (ref "R17") (pin "2") (pinfunction "2_2") (pintype "input"))
      (node (ref "R27") (pin "2") (pinfunction "2_2") (pintype "input"))
      (node (ref "SW1") (pin "2") (pinfunction "2_2") (pintype "input"))
      (node (ref "U10") (pin "5") (pinfunction "NC/VIO_5") (pintype "unspecified"))
      (node (ref "U11") (pin "5") (pinfunction "NC/VIO_5") (pintype "unspecified"))
      (node (ref "U3") (pin "2") (pinfunction "VOUT(TAB)_2") (pintype "unspecified"))
      (node (ref "U3") (pin "4") (pinfunction "TAB_4") (pintype "unspecified"))
      (node (ref "U6") (pin "5") (pinfunction "VCC_5") (pintype "unspecified"))
      (node (ref "U7") (pin "5") (pinfunction "VCC_5") (pintype "unspecified"))
      (node (ref "U8") (pin "5") (pinfunction "VCC_5") (pintype "unspecified"))
      (node (ref "U9") (pin "3") (pinfunction "3V3_3") (pintype "unspecified"))
    )
    (net (code "2") (name "+5V") (class "Default")
      (node (ref "C11") (pin "1") (pinfunction "1_1") (pintype "unspecified"))
      (node (ref "C21") (pin "2") (pinfunction "2_2") (pintype "input"))
      (node (ref "C22") (pin "2") (pinfunction "2_2") (pintype "input"))
      (node (ref "C7") (pin "2") (pinfunction "2_2") (pintype "unspecified"))
      (node (ref "R1") (pin "2") (pinfunction "2_2") (pintype "input"))
      (node (ref "U10") (pin "3") (pinfunction "VCC_3") (pintype "unspecified"))
      (node (ref "U11") (pin "3") (pinfunction "VCC_3") (pintype "unspecified"))
      (node (ref "U2") (pin "2") (pinfunction "VO-_2") (pintype "unspecified"))
      (node (ref "U3") (pin "3") (pinfunction "VIN_3") (pintype "unspecified"))
      (node (ref "U5") (pin "2") (pinfunction "VO-_2") (pintype "unspecified"))
    )
    (net (code "3") (name "BOOT") (class "Default")
      (node (ref "SW3") (pin "2") (pinfunction "2_2") (pintype "unspecified"))
      (node (ref "U9") (pin "23") (pinfunction "IO9_23") (pintype "unspecified"))
    )
    (net (code "4") (name "BRAKE_IN") (class "Default")
      (node (ref "D5") (pin "5") (pinfunction "5_5") (pintype "input"))
      (node (ref "P1") (pin "8") (pinfunction "8_8") (pintype "unspecified"))
      (node (ref "R8") (pin "2") (pinfunction "2_2") (pintype "input"))
    )
    (net (code "5") (name "BRAKE_OUT") (class "Default")
      (node (ref "D5") (pin "6") (pinfunction "6_6") (pintype "input"))
      (node (ref "P1") (pin "9") (pinfunction "9_9") (pintype "unspecified"))
      (node (ref "Q1") (pin "7") (pinfunction "D1_7") (pintype "unspecified"))
      (node (ref "Q1") (pin "8") (pinfunction "D1_8") (pintype "unspecified"))
    )
    (net (code "6") (name "BST") (class "Default")
      (node (ref "C1") (pin "2") (pinfunction "2_2") (pintype "unspecified"))
      (node (ref "U1") (pin "6") (pinfunction "BST_6") (pintype "input"))
    )
    (net (code "7") (name "BUCK_OUT") (class "Default")
      (node (ref "C5") (pin "2") (pinfunction "2_2") (pintype "unspecified"))
      (node (ref "C6") (pin "2") (pinfunction "2_2") (pintype "unspecified"))
      (node (ref "L1") (pin "2") (pinfunction "2_2") (pintype "unspecified"))
      (node (ref "R3") (pin "2") (pinfunction "2_2") (pintype "input"))
      (node (ref "U2") (pin "3") (pinfunction "VI+_3") (pintype "unspecified"))
    )
    (net (code "8") (name "CAN0_RX") (class "Default")
      (node (ref "U10") (pin "4") (pinfunction "RXD_4") (pintype "unspecified"))
      (node (ref "U9") (pin "29") (pinfunction "IO23_29") (pintype "unspecified"))
    )
    (net (code "9") (name "CAN0_STANDBY") (class "Default")
      (node (ref "R25") (pin "1") (pinfunction "1_1") (pintype "input"))
      (node (ref "U10") (pin "8") (pinfunction "STB_8") (pintype "unspecified"))
      (node (ref "U9") (pin "5") (pinfunction "IO2_5") (pintype "unspecified"))
    )
    (net (code "10") (name "CAN0_TX") (class "Default")
      (node (ref "U10") (pin "1") (pinfunction "TXD_1") (pintype "unspecified"))
      (node (ref "U9") (pin "6") (pinfunction "IO3_6") (pintype "unspecified"))
    )
    (net (code "11") (name "CAN1_RX") (class "Default")
      (node (ref "U11") (pin "4") (pinfunction "RXD_4") (pintype "unspecified"))
      (node (ref "U9") (pin "26") (pinfunction "IO20_26") (pintype "unspecified"))
    )
    (net (code "12") (name "CAN1_STANDBY") (class "Default")
      (node (ref "R26") (pin "1") (pinfunction "1_1") (pintype "input"))
      (node (ref "U11") (pin "8") (pinfunction "STB_8") (pintype "unspecified"))
      (node (ref "U9") (pin "28") (pinfunction "IO22_28") (pintype "unspecified"))
    )
    (net (code "13") (name "CAN1_TX") (class "Default")
      (node (ref "U11") (pin "1") (pinfunction "TXD_1") (pintype "unspecified"))
      (node (ref "U9") (pin "27") (pinfunction "IO21_27") (pintype "unspecified"))
    )
    (net (code "14") (name "CC1") (class "Default")
      (node (ref "R6") (pin "2") (pinfunction "2_2") (pintype "input"))
      (node (ref "USB1") (pin "4") (pinfunction "CC1_4") (pintype "unspecified"))
    )
    (net (code "15") (name "CC2") (class "Default")
      (node (ref "R7") (pin "2") (pinfunction "2_2") (pintype "input"))
      (node (ref "USB1") (pin "10") (pinfunction "CC2_10") (pintype "unspecified"))
    )
    (net (code "16") (name "CHASSIS_CANH") (class "Default")
      (node (ref "D9") (pin "1") (pinfunction "1_1") (pintype "unspecified"))
      (node (ref "P1") (pin "4") (pinfunction "4_4") (pintype "unspecified"))
      (node (ref "R21") (pin "2") (pinfunction "2_2") (pintype "unspecified"))
      (node (ref "U10") (pin "7") (pinfunction "CANH_7") (pintype "unspecified"))
    )
    (net (code "17") (name "CHASSIS_CANL") (class "Default")
      (node (ref "D9") (pin "2") (pinfunction "2_2") (pintype "unspecified"))
      (node (ref "P1") (pin "3") (pinfunction "3_3") (pintype "unspecified"))
      (node (ref "R23") (pin "1") (pinfunction "1_1") (pintype "unspecified"))
      (node (ref "U10") (pin "6") (pinfunction "CANL_6") (pintype "unspecified"))
    )
    (net (code "18") (name "D+") (class "Default")
      (node (ref "R19") (pin "2") (pinfunction "2_2") (pintype "input"))
      (node (ref "U9") (pin "18") (pinfunction "IO13_18") (pintype "unspecified"))
    )
    (net (code "19") (name "D-") (class "Default")
      (node (ref "R18") (pin "2") (pinfunction "2_2") (pintype "input"))
      (node (ref "U9") (pin "17") (pinfunction "IO12_17") (pintype "unspecified"))
    )
    (net (code "20") (name "EN_TPS") (class "Default")
      (node (ref "U1") (pin "2") (pinfunction "EN_2") (pintype "input"))
    )
    (net (code "21") (name "ESP_BRAKE_IN") (class "Default")
      (node (ref "U6") (pin "4") (pinfunction "Y_4") (pintype "unspecified"))
      (node (ref "U9") (pin "12") (pinfunction "IO0_12") (pintype "unspecified"))
    )
    (net (code "22") (name "ESP_BRAKE_OUT") (class "Default")
      (node (ref "R13") (pin "1") (pinfunction "1_1") (pintype "input"))
      (node (ref "U9") (pin "13") (pinfunction "IO1_13") (pintype "unspecified"))
    )
    (net (code "23") (name "ESP_BRAKE_TRANS") (class "Default")
      (node (ref "Q2") (pin "2") (pinfunction "G1_2") (pintype "unspecified"))
      (node (ref "R13") (pin "2") (pinfunction "2_2") (pintype "input"))
    )
    (net (code "24") (name "ESP_HB_IN") (class "Default")
      (node (ref "U7") (pin "4") (pinfunction "Y_4") (pintype "unspecified"))
      (node (ref "U9") (pin "19") (pinfunction "IO14_19") (pintype "unspecified"))
    )
    (net (code "25") (name "ESP_HB_OUT") (class "Default")
      (node (ref "R16") (pin "1") (pinfunction "1_1") (pintype "input"))
      (node (ref "U9") (pin "20") (pinfunction "IO15_20") (pintype "unspecified"))
    )
    (net (code "26") (name "ESP_HB_TRANS") (class "Default")
      (node (ref "Q2") (pin "5") (pinfunction "G2_5") (pintype "unspecified"))
      (node (ref "R16") (pin "2") (pinfunction "2_2") (pintype "input"))
    )
    (net (code "27") (name "ESP_SWITCH_MODE_EXT") (class "Default")
      (node (ref "U8") (pin "4") (pinfunction "Y_4") (pintype "unspecified"))
      (node (ref "U9") (pin "24") (pinfunction "IO18_24") (pintype "unspecified"))
    )
    (net (code "28") (name "ESP_USB_D+") (class "Default")
      (node (ref "D3") (pin "1") (pinfunction "I/O1_1") (pintype "unspecified"))
      (node (ref "R19") (pin "1") (pinfunction "1_1") (pintype "input"))
    )
    (net (code "29") (name "ESP_USB_D-") (class "Default")
      (node (ref "D3") (pin "3") (pinfunction "I/O2_3") (pintype "unspecified"))
      (node (ref "R18") (pin "1") (pinfunction "1_1") (pintype "input"))
    )
    (net (code "30") (name "FB") (class "Default")
      (node (ref "R3") (pin "1") (pinfunction "1_1") (pintype "input"))
      (node (ref "R5") (pin "2") (pinfunction "2_2") (pintype "input"))
      (node (ref "U1") (pin "8") (pinfunction "FB_8") (pintype "input"))
    )
    (net (code "31") (name "GND") (class "Default")
      (node (ref "C10") (pin "2") (pinfunction "2_2") (pintype "unspecified"))
      (node (ref "C11") (pin "2") (pinfunction "2_2") (pintype "unspecified"))
      (node (ref "C12") (pin "1") (pinfunction "1_1") (pintype "unspecified"))
      (node (ref "C13") (pin "1") (pinfunction "1_1") (pintype "unspecified"))
      (node (ref "C14") (pin "1") (pinfunction "1_1") (pintype "unspecified"))
      (node (ref "C15") (pin "2") (pinfunction "2_2") (pintype "input"))
      (node (ref "C16") (pin "2") (pinfunction "2_2") (pintype "input"))
      (node (ref "C17") (pin "2") (pinfunction "2_2") (pintype "input"))
      (node (ref "C18") (pin "2") (pinfunction "2_2") (pintype "unspecified"))
      (node (ref "C19") (pin "1") (pinfunction "1_1") (pintype "input"))
      (node (ref "C2") (pin "2") (pinfunction "2_2") (pintype "unspecified"))
      (node (ref "C20") (pin "1") (pinfunction "1_1") (pintype "input"))
      (node (ref "C21") (pin "1") (pinfunction "1_1") (pintype "input"))
      (node (ref "C22") (pin "1") (pinfunction "1_1") (pintype "input"))
      (node (ref "C23") (pin "2") (pinfunction "2_2") (pintype "input"))
      (node (ref "C24") (pin "2") (pinfunction "2_2") (pintype "input"))
      (node (ref "C3") (pin "2") (pinfunction "2_2") (pintype "unspecified"))
      (node (ref "C4") (pin "1") (pinfunction "1_1") (pintype "unspecified"))
      (node (ref "C5") (pin "1") (pinfunction "1_1") (pintype "unspecified"))
      (node (ref "C6") (pin "1") (pinfunction "1_1") (pintype "unspecified"))
      (node (ref "C7") (pin "1") (pinfunction "1_1") (pintype "unspecified"))
      (node (ref "C8") (pin "1") (pinfunction "1_1") (pintype "unspecified"))
      (node (ref "C9") (pin "1") (pinfunction "1_1") (pintype "unspecified"))
      (node (ref "D10") (pin "3") (pinfunction "3_3") (pintype "unspecified"))
      (node (ref "D11") (pin "2") (pinfunction "A_2") (pintype "unspecified"))
      (node (ref "D2") (pin "1") (pinfunction "1_1") (pintype "input"))
      (node (ref "D3") (pin "2") (pinfunction "GND_2") (pintype "unspecified"))
      (node (ref "D4") (pin "2") (pinfunction "A_2") (pintype "unspecified"))
      (node (ref "D5") (pin "2") (pinfunction "2_2") (pintype "input"))
      (node (ref "D6") (pin "2") (pinfunction "A_2") (pintype "unspecified"))
      (node (ref "D7") (pin "2") (pinfunction "A_2") (pintype "unspecified"))
      (node (ref "D8") (pin "2") (pinfunction "2_2") (pintype "input"))
      (node (ref "D9") (pin "3") (pinfunction "3_3") (pintype "unspecified"))
      (node (ref "H1") (pin "6") (pinfunction "6_6") (pintype "unspecified"))
      (node (ref "LED1") (pin "1") (pinfunction "K_1") (pintype "input"))
      (node (ref "LED2") (pin "3") (pinfunction "GND_3") (pintype "unspecified"))
      (node (ref "P1") (pin "2") (pinfunction "2_2") (pintype "unspecified"))
      (node (ref "Q2") (pin "1") (pinfunction "S1_1") (pintype "unspecified"))
      (node (ref "Q2") (pin "4") (pinfunction "S2_4") (pintype "unspecified"))
      (node (ref "R2") (pin "1") (pinfunction "1_1") (pintype "unspecified"))
      (node (ref "R20") (pin "1") (pinfunction "1_1") (pintype "input"))
      (node (ref "R25") (pin "2") (pinfunction "2_2") (pintype "input"))
      (node (ref "R26") (pin "2") (pinfunction "2_2") (pintype "input"))
      (node (ref "R4") (pin "1") (pinfunction "1_1") (pintype "input"))
      (node (ref "R5") (pin "1") (pinfunction "1_1") (pintype "input"))
      (node (ref "R6") (pin "1") (pinfunction "1_1") (pintype "input"))
      (node (ref "R7") (pin "1") (pinfunction "1_1") (pintype "input"))
      (node (ref "SW2") (pin "1") (pinfunction "1_1") (pintype "unspecified"))
      (node (ref "SW3") (pin "1") (pinfunction "1_1") (pintype "unspecified"))
      (node (ref "U1") (pin "4") (pinfunction "GND_4") (pintype "input"))
      (node (ref "U10") (pin "2") (pinfunction "GND_2") (pintype "unspecified"))
      (node (ref "U10") (pin "9") (pinfunction "EP_9") (pintype "unspecified"))
      (node (ref "U11") (pin "2") (pinfunction "GND_2") (pintype "unspecified"))
      (node (ref "U11") (pin "9") (pinfunction "EP_9") (pintype "unspecified"))
      (node (ref "U2") (pin "1") (pinfunction "GND_1") (pintype "unspecified"))
      (node (ref "U3") (pin "1") (pinfunction "ADJ(GND)_1") (pintype "unspecified"))
      (node (ref "U5") (pin "1") (pinfunction "GND_1") (pintype "unspecified"))
      (node (ref "U6") (pin "3") (pinfunction "GND_3") (pintype "unspecified"))
      (node (ref "U7") (pin "3") (pinfunction "GND_3") (pintype "unspecified"))
      (node (ref "U8") (pin "3") (pinfunction "GND_3") (pintype "unspecified"))
      (node (ref "U9") (pin "1") (pinfunction "GND_1") (pintype "unspecified"))
      (node (ref "U9") (pin "11") (pinfunction "GND_11") (pintype "unspecified"))
      (node (ref "U9") (pin "14") (pinfunction "GND_14") (pintype "unspecified"))
      (node (ref "U9") (pin "2") (pinfunction "GND_2") (pintype "unspecified"))
      (node (ref "U9") (pin "36") (pinfunction "GND_36") (pintype "unspecified"))
      (node (ref "U9") (pin "37") (pinfunction "GND_37") (pintype "unspecified"))
      (node (ref "U9") (pin "38") (pinfunction "GND_38") (pintype "unspecified"))
      (node (ref "U9") (pin "39") (pinfunction "GND_39") (pintype "unspecified"))
      (node (ref "U9") (pin "40") (pinfunction "GND_40") (pintype "unspecified"))
      (node (ref "U9") (pin "41") (pinfunction "GND_41") (pintype "unspecified"))
      (node (ref "U9") (pin "42") (pinfunction "GND_42") (pintype "unspecified"))
      (node (ref "U9") (pin "43") (pinfunction "GND_43") (pintype "unspecified"))
      (node (ref "U9") (pin "44") (pinfunction "GND_44") (pintype "unspecified"))
      (node (ref "U9") (pin "45") (pinfunction "GND_45") (pintype "unspecified"))
      (node (ref "U9") (pin "46") (pinfunction "GND_46") (pintype "unspecified"))
      (node (ref "U9") (pin "47") (pinfunction "GND_47") (pintype "unspecified"))
      (node (ref "U9") (pin "48") (pinfunction "GND_48") (pintype "unspecified"))
      (node (ref "U9") (pin "49") (pinfunction "GND_49") (pintype "unspecified"))
      (node (ref "U9") (pin "50") (pinfunction "GND_50") (pintype "unspecified"))
      (node (ref "U9") (pin "51") (pinfunction "GND_51") (pintype "unspecified"))
      (node (ref "U9") (pin "52") (pinfunction "GND_52") (pintype "unspecified"))
      (node (ref "U9") (pin "53") (pinfunction "GND_53") (pintype "unspecified"))
      (node (ref "USB1") (pin "1") (pinfunction "GND_1") (pintype "unspecified"))
      (node (ref "USB1") (pin "12") (pinfunction "GND_12") (pintype "unspecified"))
      (node (ref "USB1") (pin "13") (pinfunction "SHELL_13") (pintype "unspecified"))
      (node (ref "USB1") (pin "14") (pinfunction "SHELL_14") (pintype "unspecified"))
    )
    (net (code "32") (name "HALDEX_CANH") (class "Default")
      (node (ref "D10") (pin "1") (pinfunction "1_1") (pintype "unspecified"))
      (node (ref "P1") (pin "6") (pinfunction "6_6") (pintype "unspecified"))
      (node (ref "R22") (pin "2") (pinfunction "2_2") (pintype "unspecified"))
      (node (ref "U11") (pin "7") (pinfunction "CANH_7") (pintype "unspecified"))
    )
    (net (code "33") (name "HALDEX_CANL") (class "Default")
      (node (ref "D10") (pin "2") (pinfunction "2_2") (pintype "unspecified"))
      (node (ref "P1") (pin "5") (pinfunction "5_5") (pintype "unspecified"))
      (node (ref "R24") (pin "1") (pinfunction "1_1") (pintype "unspecified"))
      (node (ref "U11") (pin "6") (pinfunction "CANL_6") (pintype "unspecified"))
    )
    (net (code "34") (name "HB_IN") (class "Default")
      (node (ref "D5") (pin "1") (pinfunction "1_1") (pintype "input"))
      (node (ref "P1") (pin "10") (pinfunction "10_10") (pintype "unspecified"))
      (node (ref "R9") (pin "2") (pinfunction "2_2") (pintype "input"))
    )
    (net (code "35") (name "HB_OUT") (class "Default")
      (node (ref "D5") (pin "3") (pinfunction "3_3") (pintype "input"))
      (node (ref "P1") (pin "11") (pinfunction "11_11") (pintype "unspecified"))
      (node (ref "Q1") (pin "5") (pinfunction "D2_5") (pintype "unspecified"))
      (node (ref "Q1") (pin "6") (pinfunction "D2_6") (pintype "unspecified"))
    )
    (net (code "36") (name "MTCK") (class "Default")
      (node (ref "D8") (pin "3") (pinfunction "3_3") (pintype "input"))
      (node (ref "H1") (pin "2") (pinfunction "2_2") (pintype "unspecified"))
      (node (ref "U9") (pin "15") (pinfunction "IO6_15") (pintype "unspecified"))
    )
    (net (code "37") (name "MTDI") (class "Default")
      (node (ref "D8") (pin "5") (pinfunction "5_5") (pintype "input"))
      (node (ref "H1") (pin "3") (pinfunction "3_3") (pintype "unspecified"))
      (node (ref "U9") (pin "10") (pinfunction "IO5_10") (pintype "unspecified"))
    )
    (net (code "38") (name "MTDO") (class "Default")
      (node (ref "D8") (pin "1") (pinfunction "1_1") (pintype "input"))
      (node (ref "H1") (pin "4") (pinfunction "4_4") (pintype "unspecified"))
      (node (ref "U9") (pin "16") (pinfunction "IO7_16") (pintype "unspecified"))
    )
    (net (code "39") (name "MTMS") (class "Default")
      (node (ref "D8") (pin "6") (pinfunction "6_6") (pintype "input"))
      (node (ref "H1") (pin "5") (pinfunction "5_5") (pintype "unspecified"))
      (node (ref "U9") (pin "9") (pinfunction "IO4_9") (pintype "unspecified"))
    )
    (net (code "40") (name "Net-(C19-Pad2)") (class "Default")
      (node (ref "C19") (pin "2") (pinfunction "2_2") (pintype "input"))
      (node (ref "R21") (pin "1") (pinfunction "1_1") (pintype "unspecified"))
      (node (ref "R23") (pin "2") (pinfunction "2_2") (pintype "unspecified"))
    )
    (net (code "41") (name "Net-(C20-Pad2)") (class "Default")
      (node (ref "C20") (pin "2") (pinfunction "2_2") (pintype "input"))
      (node (ref "R22") (pin "1") (pinfunction "1_1") (pintype "unspecified"))
      (node (ref "R24") (pin "2") (pinfunction "2_2") (pintype "unspecified"))
    )
    (net (code "42") (name "Net-(D4-K)") (class "Default")
      (node (ref "D4") (pin "1") (pinfunction "K_1") (pintype "unspecified"))
      (node (ref "R8") (pin "1") (pinfunction "1_1") (pintype "input"))
      (node (ref "U6") (pin "2") (pinfunction "A_2") (pintype "unspecified"))
    )
    (net (code "43") (name "Net-(D6-K)") (class "Default")
      (node (ref "D6") (pin "1") (pinfunction "K_1") (pintype "unspecified"))
      (node (ref "R9") (pin "1") (pinfunction "1_1") (pintype "input"))
      (node (ref "U7") (pin "2") (pinfunction "A_2") (pintype "unspecified"))
    )
    (net (code "44") (name "Net-(D7-K)") (class "Default")
      (node (ref "D7") (pin "1") (pinfunction "K_1") (pintype "unspecified"))
      (node (ref "R11") (pin "1") (pinfunction "1_1") (pintype "input"))
      (node (ref "U8") (pin "2") (pinfunction "A_2") (pintype "unspecified"))
    )
    (net (code "45") (name "Net-(LED1-A)") (class "Default")
      (node (ref "LED1") (pin "2") (pinfunction "A_2") (pintype "input"))
      (node (ref "R1") (pin "1") (pinfunction "1_1") (pintype "input"))
    )
    (net (code "46") (name "Net-(Q1-G1)") (class "Default")
      (node (ref "Q1") (pin "2") (pinfunction "G1_2") (pintype "unspecified"))
      (node (ref "R10") (pin "1") (pinfunction "1_1") (pintype "input"))
      (node (ref "R12") (pin "2") (pinfunction "2_2") (pintype "input"))
    )
    (net (code "47") (name "Net-(Q1-G2)") (class "Default")
      (node (ref "Q1") (pin "4") (pinfunction "G2_4") (pintype "unspecified"))
      (node (ref "R14") (pin "1") (pinfunction "1_1") (pintype "input"))
      (node (ref "R15") (pin "1") (pinfunction "1_1") (pintype "input"))
    )
    (net (code "48") (name "Net-(Q2A-D1)") (class "Default")
      (node (ref "Q2") (pin "6") (pinfunction "D1_6") (pintype "unspecified"))
      (node (ref "R12") (pin "1") (pinfunction "1_1") (pintype "input"))
    )
    (net (code "49") (name "Net-(Q2B-D2)") (class "Default")
      (node (ref "Q2") (pin "3") (pinfunction "D2_3") (pintype "unspecified"))
      (node (ref "R15") (pin "2") (pinfunction "2_2") (pintype "input"))
    )
    (net (code "50") (name "RESET") (class "Default")
      (node (ref "D8") (pin "4") (pinfunction "4_4") (pintype "input"))
      (node (ref "H1") (pin "1") (pinfunction "1_1") (pintype "unspecified"))
      (node (ref "R27") (pin "1") (pinfunction "1_1") (pintype "input"))
      (node (ref "SW2") (pin "2") (pinfunction "2_2") (pintype "unspecified"))
      (node (ref "U9") (pin "8") (pinfunction "EN_8") (pintype "unspecified"))
    )
    (net (code "51") (name "RGB_LED") (class "Default")
      (node (ref "LED2") (pin "4") (pinfunction "Din_4") (pintype "unspecified"))
      (node (ref "R17") (pin "1") (pinfunction "1_1") (pintype "input"))
      (node (ref "U9") (pin "22") (pinfunction "IO8_22") (pintype "unspecified"))
    )
    (net (code "52") (name "RT") (class "Default")
      (node (ref "R4") (pin "2") (pinfunction "2_2") (pintype "input"))
      (node (ref "U1") (pin "1") (pinfunction "RT_1") (pintype "input"))
    )
    (net (code "53") (name "SS") (class "Default")
      (node (ref "C9") (pin "2") (pinfunction "2_2") (pintype "unspecified"))
      (node (ref "U1") (pin "7") (pinfunction "SS_7") (pintype "input"))
    )
    (net (code "54") (name "SW") (class "Default")
      (node (ref "C1") (pin "1") (pinfunction "1_1") (pintype "unspecified"))
      (node (ref "L1") (pin "1") (pinfunction "1_1") (pintype "unspecified"))
      (node (ref "U1") (pin "5") (pinfunction "SW_5") (pintype "input"))
    )
    (net (code "55") (name "SWITCH_MODE") (class "Default")
      (node (ref "C18") (pin "1") (pinfunction "1_1") (pintype "unspecified"))
      (node (ref "R20") (pin "2") (pinfunction "2_2") (pintype "input"))
      (node (ref "SW1") (pin "4") (pinfunction "4_4") (pintype "input"))
      (node (ref "U9") (pin "25") (pinfunction "IO19_25") (pintype "unspecified"))
    )
    (net (code "56") (name "SWITCH_MODE_EXT") (class "Default")
      (node (ref "D5") (pin "4") (pinfunction "4_4") (pintype "input"))
      (node (ref "P1") (pin "7") (pinfunction "7_7") (pintype "unspecified"))
      (node (ref "R11") (pin "2") (pinfunction "2_2") (pintype "input"))
    )
    (net (code "57") (name "USB_D+") (class "Default")
      (node (ref "D3") (pin "6") (pinfunction "I/O1_6") (pintype "unspecified"))
      (node (ref "USB1") (pin "6") (pinfunction "DP1_6") (pintype "unspecified"))
      (node (ref "USB1") (pin "8") (pinfunction "DP2_8") (pintype "unspecified"))
    )
    (net (code "58") (name "USB_D-") (class "Default")
      (node (ref "D3") (pin "4") (pinfunction "I/O2_4") (pintype "unspecified"))
      (node (ref "USB1") (pin "5") (pinfunction "DN2_5") (pintype "unspecified"))
      (node (ref "USB1") (pin "7") (pinfunction "DN1_7") (pintype "unspecified"))
    )
    (net (code "59") (name "VBAT") (class "Default")
      (node (ref "D1") (pin "2") (pinfunction "A_2") (pintype "unspecified"))
      (node (ref "D2") (pin "2") (pinfunction "2_2") (pintype "input"))
      (node (ref "P1") (pin "1") (pinfunction "1_1") (pintype "unspecified"))
      (node (ref "R2") (pin "2") (pinfunction "2_2") (pintype "unspecified"))
    )
    (net (code "60") (name "VBAT_UF") (class "Default")
      (node (ref "D1") (pin "1") (pinfunction "C_1") (pintype "unspecified"))
      (node (ref "F1") (pin "1") (pinfunction "1_1") (pintype "input"))
    )
    (net (code "61") (name "VBUS") (class "Default")
      (node (ref "C10") (pin "1") (pinfunction "1_1") (pintype "unspecified"))
      (node (ref "D3") (pin "5") (pinfunction "VBUS_5") (pintype "unspecified"))
      (node (ref "U5") (pin "3") (pinfunction "VI+_3") (pintype "unspecified"))
      (node (ref "USB1") (pin "11") (pinfunction "VBUS_11") (pintype "unspecified"))
      (node (ref "USB1") (pin "2") (pinfunction "VBUS_2") (pintype "unspecified"))
    )
    (net (code "62") (name "VCC") (class "Default")
      (node (ref "C2") (pin "1") (pinfunction "1_1") (pintype "unspecified"))
      (node (ref "C3") (pin "1") (pinfunction "1_1") (pintype "unspecified"))
      (node (ref "C4") (pin "2") (pinfunction "2_2") (pintype "unspecified"))
      (node (ref "D11") (pin "1") (pinfunction "K_1") (pintype "unspecified"))
      (node (ref "F1") (pin "2") (pinfunction "2_2") (pintype "input"))
      (node (ref "Q1") (pin "1") (pinfunction "S1_1") (pintype "unspecified"))
      (node (ref "Q1") (pin "3") (pinfunction "S2_3") (pintype "unspecified"))
      (node (ref "R10") (pin "2") (pinfunction "2_2") (pintype "input"))
      (node (ref "R14") (pin "2") (pinfunction "2_2") (pintype "input"))
      (node (ref "U1") (pin "3") (pinfunction "VIN_3") (pintype "input"))
    )
    (net (code "63") (name "unconnected-(LED2-Dout-Pad1)") (class "Default")
      (node (ref "LED2") (pin "1") (pinfunction "Dout_1") (pintype "unspecified+no_connect"))
    )
    (net (code "64") (name "unconnected-(P1-Pad12)") (class "Default")
      (node (ref "P1") (pin "12") (pinfunction "12_12") (pintype "unspecified+no_connect"))
    )
    (net (code "65") (name "unconnected-(SW1-Pad1)") (class "Default")
      (node (ref "SW1") (pin "1") (pinfunction "1_1") (pintype "input+no_connect"))
    )
    (net (code "66") (name "unconnected-(SW1-Pad3)") (class "Default")
      (node (ref "SW1") (pin "3") (pinfunction "3_3") (pintype "input+no_connect"))
    )
    (net (code "67") (name "unconnected-(U6-N.C-Pad1)") (class "Default")
      (node (ref "U6") (pin "1") (pinfunction "N.C_1") (pintype "unspecified+no_connect"))
    )
    (net (code "68") (name "unconnected-(U7-N.C-Pad1)") (class "Default")
      (node (ref "U7") (pin "1") (pinfunction "N.C_1") (pintype "unspecified+no_connect"))
    )
    (net (code "69") (name "unconnected-(U8-N.C-Pad1)") (class "Default")
      (node (ref "U8") (pin "1") (pinfunction "N.C_1") (pintype "unspecified+no_connect"))
    )
    (net (code "70") (name "unconnected-(U9-NC-Pad4)") (class "Default")
      (node (ref "U9") (pin "4") (pinfunction "NC_4") (pintype "unspecified+no_connect"))
    )
    (net (code "71") (name "unconnected-(U9-NC-Pad7)") (class "Default")
      (node (ref "U9") (pin "7") (pinfunction "NC_7") (pintype "unspecified+no_connect"))
    )
    (net (code "72") (name "unconnected-(U9-NC-Pad21)") (class "Default")
      (node (ref "U9") (pin "21") (pinfunction "NC_21") (pintype "unspecified+no_connect"))
    )
    (net (code "73") (name "unconnected-(U9-NC-Pad32)") (class "Default")
      (node (ref "U9") (pin "32") (pinfunction "NC_32") (pintype "unspecified+no_connect"))
    )
    (net (code "74") (name "unconnected-(U9-NC-Pad33)") (class "Default")
      (node (ref "U9") (pin "33") (pinfunction "NC_33") (pintype "unspecified+no_connect"))
    )
    (net (code "75") (name "unconnected-(U9-NC-Pad34)") (class "Default")
      (node (ref "U9") (pin "34") (pinfunction "NC_34") (pintype "unspecified+no_connect"))
    )
    (net (code "76") (name "unconnected-(U9-NC-Pad35)") (class "Default")
      (node (ref "U9") (pin "35") (pinfunction "NC_35") (pintype "unspecified+no_connect"))
    )
    (net (code "77") (name "unconnected-(U9-RXD0-Pad30)") (class "Default")
      (node (ref "U9") (pin "30") (pinfunction "RXD0_30") (pintype "unspecified+no_connect"))
    )
    (net (code "78") (name "unconnected-(U9-TXD0-Pad31)") (class "Default")
      (node (ref "U9") (pin "31") (pinfunction "TXD0_31") (pintype "unspecified+no_connect"))
    )
    (net (code "79") (name "unconnected-(USB1-SBU1-Pad9)") (class "Default")
      (node (ref "USB1") (pin "9") (pinfunction "SBU1_9") (pintype "unspecified+no_connect"))
    )
    (net (code "80") (name "unconnected-(USB1-SBU2-Pad3)") (class "Default")
      (node (ref "USB1") (pin "3") (pinfunction "SBU2_3") (pintype "unspecified+no_connect"))
    )
  )
)
